# MikeFornoff_NFC_Card.net
KiCad netlist of a schematic drawn in EAGLE
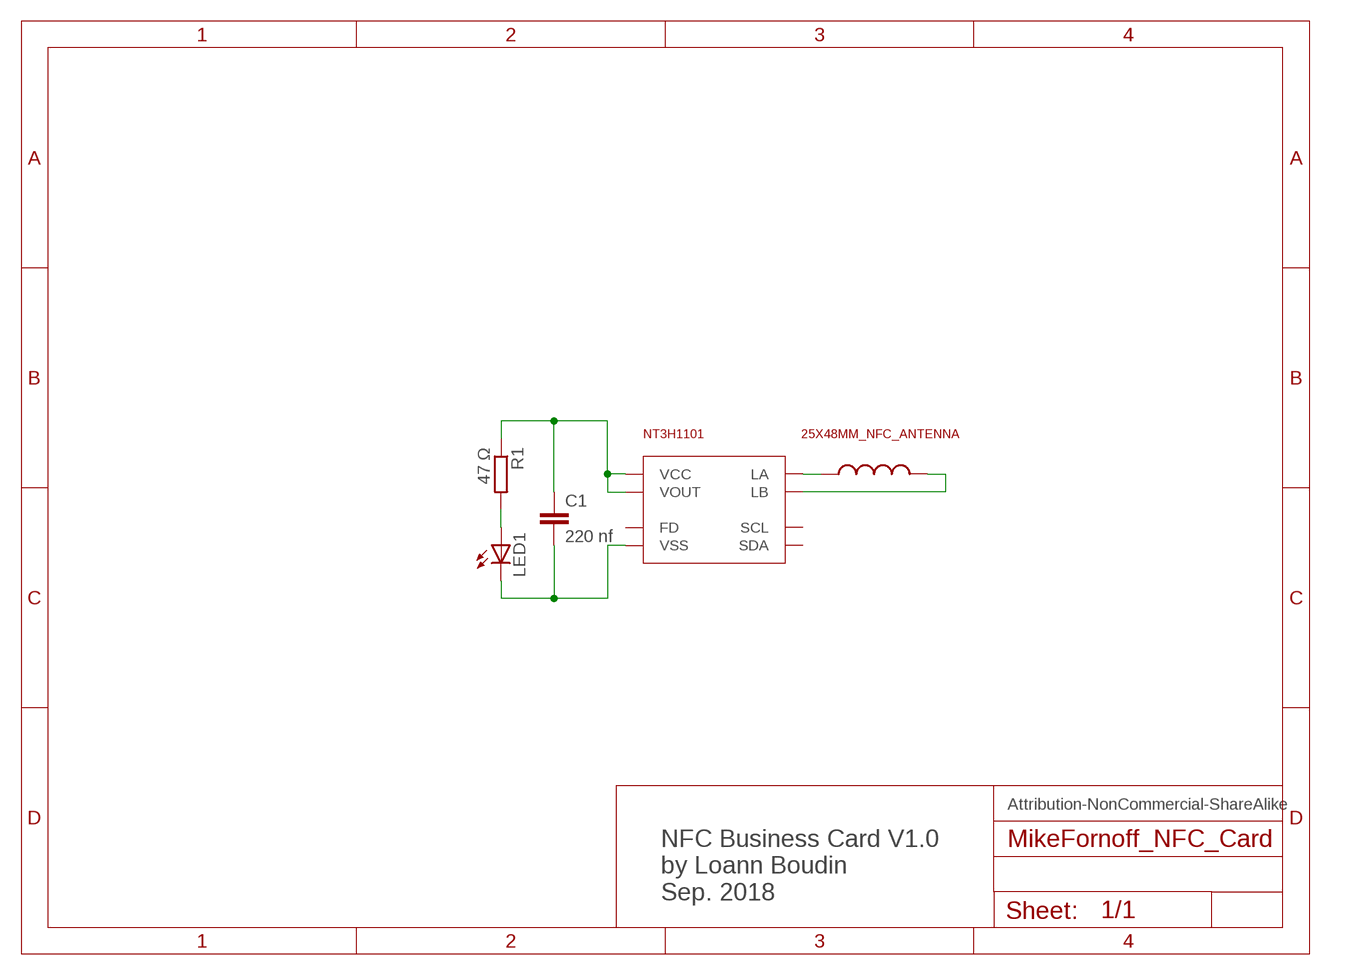
[diagram p0: schematic, sheet 1]

(export (version "E")
  (design (tool "Eeschema 10.0.6"))
  (components
    (comp (ref "ANT")
      (value "25X48MM_NFC_ANTENNA")
      (footprint "eagle-import:25X48MM_NFC")
      (libsource (lib "eagle-import") (part "25X48MM_NFC_ANTENNA"))
    )
    (comp (ref "C1")
      (value "220 nf")
      (footprint "eagle-import:C0603")
      (libsource (lib "eagle-import") (part "C-EUC0603"))
    )
    (comp (ref "LED1")
      (value "LEDSML0805")
      (footprint "eagle-import:SML0805")
      (libsource (lib "eagle-import") (part "LEDSML0805"))
    )
    (comp (ref "NT3H1101")
      (value "NT3H")
      (footprint "eagle-import:XQFN8")
      (libsource (lib "eagle-import") (part "NT3H"))
    )
    (comp (ref "R1")
      (value "47 Ω")
      (footprint "eagle-import:R0603")
      (libsource (lib "eagle-import") (part "R-EU_R0603"))
    )
  )
  (nets
    (net (code "1") (name "Net-(ANT-PadP$1)") (class "Default")
      (node (ref "ANT") (pin "P$1") (pinfunction "P$1_P$1") (pintype "bidirectional"))
      (node (ref "NT3H1101") (pin "LB") (pinfunction "LB_LB") (pintype "bidirectional"))
    )
    (net (code "2") (name "Net-(ANT-PadP$2)") (class "Default")
      (node (ref "ANT") (pin "P$2") (pinfunction "P$2_P$2") (pintype "bidirectional"))
      (node (ref "NT3H1101") (pin "LA") (pinfunction "LA_LA") (pintype "bidirectional"))
    )
    (net (code "3") (name "Net-(C1-Pad1)") (class "Default")
      (node (ref "C1") (pin "1") (pinfunction "1_1") (pintype "passive"))
      (node (ref "NT3H1101") (pin "VCC") (pinfunction "VCC_VCC") (pintype "bidirectional"))
      (node (ref "NT3H1101") (pin "VOUT") (pinfunction "VOUT_VOUT") (pintype "bidirectional"))
      (node (ref "R1") (pin "1") (pinfunction "1_1") (pintype "passive"))
    )
    (net (code "4") (name "Net-(C1-Pad2)") (class "Default")
      (node (ref "C1") (pin "2") (pinfunction "2_2") (pintype "passive"))
      (node (ref "LED1") (pin "C") (pinfunction "C_C") (pintype "passive"))
      (node (ref "NT3H1101") (pin "VSS") (pinfunction "VSS_VSS") (pintype "bidirectional"))
    )
    (net (code "5") (name "Net-(LED1-PadA)") (class "Default")
      (node (ref "LED1") (pin "A") (pinfunction "A_A") (pintype "passive"))
      (node (ref "R1") (pin "2") (pinfunction "2_2") (pintype "passive"))
    )
    (net (code "6") (name "unconnected-(NT3H1101-PadFD)") (class "Default")
      (node (ref "NT3H1101") (pin "FD") (pinfunction "FD_FD") (pintype "bidirectional"))
    )
    (net (code "7") (name "unconnected-(NT3H1101-PadSCL)") (class "Default")
      (node (ref "NT3H1101") (pin "SCL") (pinfunction "SCL_SCL") (pintype "bidirectional"))
    )
    (net (code "8") (name "unconnected-(NT3H1101-PadSDA)") (class "Default")
      (node (ref "NT3H1101") (pin "SDA") (pinfunction "SDA_SDA") (pintype "bidirectional"))
    )
  )
)
